# 06_CPU_RAM.net
KiCad netlist of a schematic drawn in Altium Designer
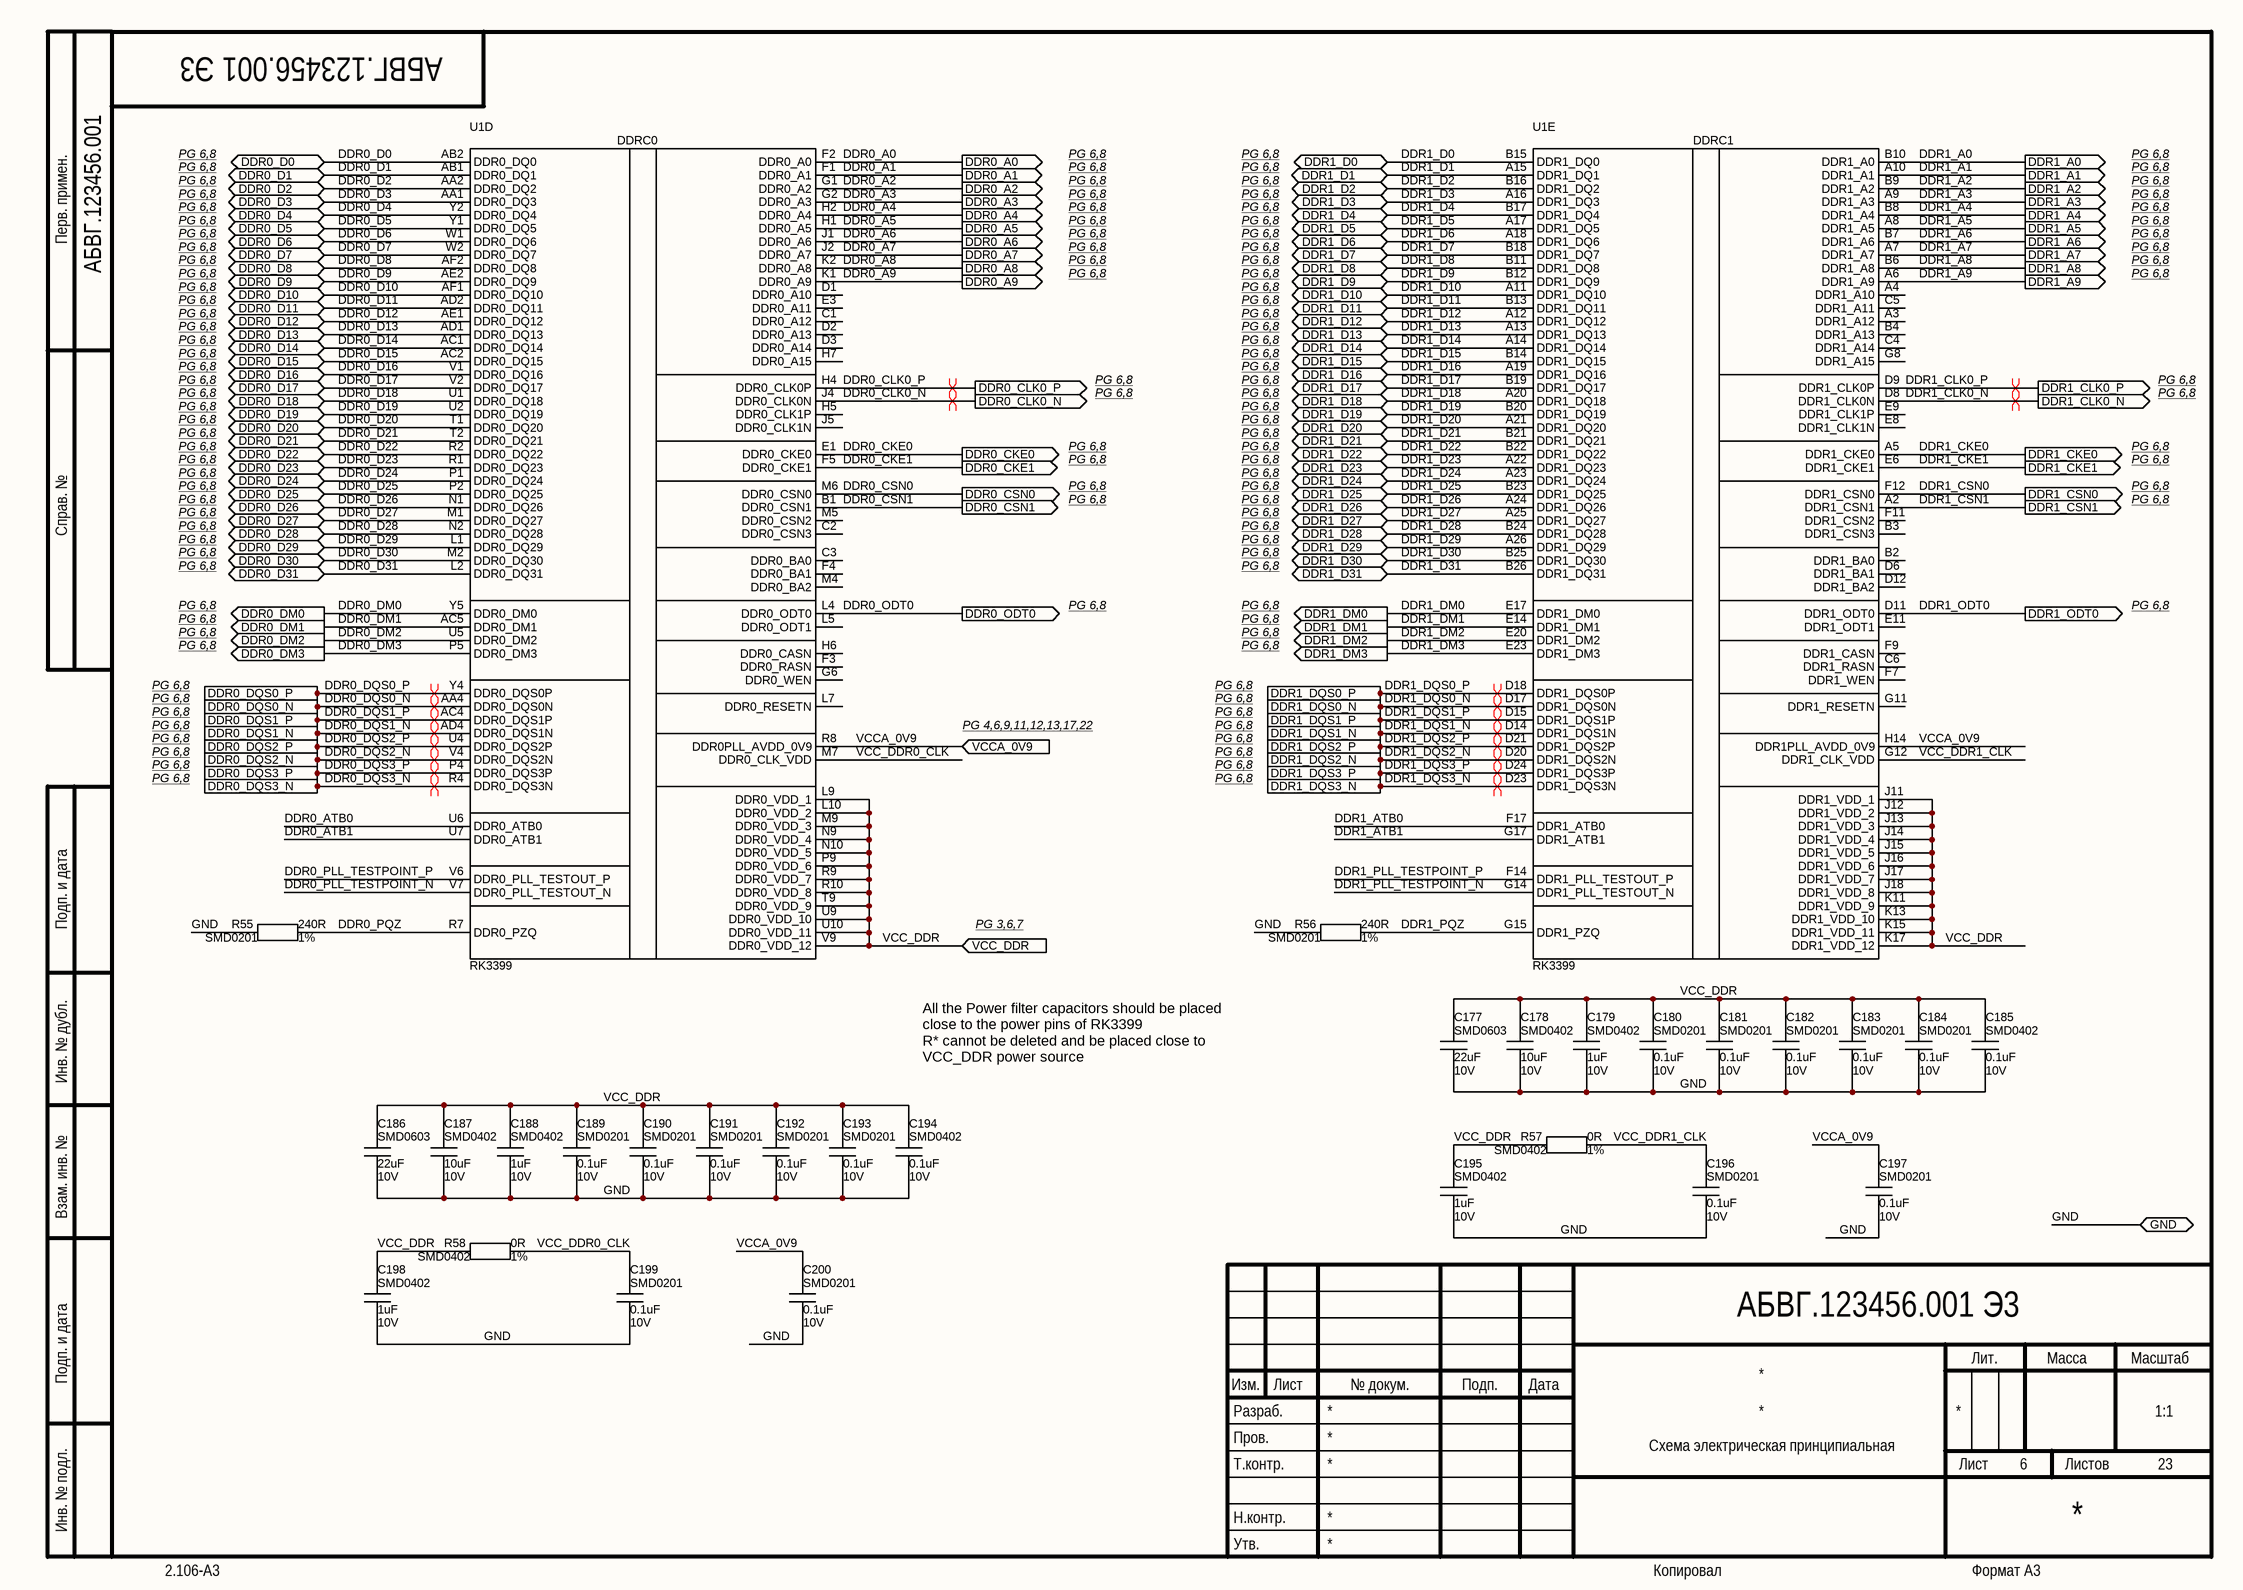
[diagram p0: 06 CPU_RAM.SchDoc]

(export (version "E")
  (design (tool "Eeschema 10.0.6"))
  (components
    (comp (ref "C177")
      (value "22uF")
      (footprint "CAP_SMD_0603")
      (fields
        (field (name "PACKAGE") "SMD0603")
        (field (name "PARTNUMBER") "CL10A226MP8NUNE")
        (field (name "VOLTAGE") "10V")
      )
      (libsource (lib "Didur_SchLib_1") (part "Ceramic_Cap"))
    )
    (comp (ref "C178")
      (value "10uF")
      (footprint "Didur_PcbLib_1:CAP_SMD_0402_small")
      (fields
        (field (name "PACKAGE") "SMD0402")
        (field (name "PARTNUMBER") "CC0402MRX5R6BB106")
        (field (name "VOLTAGE") "10V")
      )
      (libsource (lib "Didur_SchLib_1") (part "Ceramic_Cap"))
    )
    (comp (ref "C179")
      (value "1uF")
      (footprint "Didur_PcbLib_1:CAP_SMD_0402_small")
      (fields
        (field (name "PACKAGE") "SMD0402")
        (field (name "PARTNUMBER") "CC0402KRX5R6BB105")
        (field (name "VOLTAGE") "10V")
      )
      (libsource (lib "Didur_SchLib_1") (part "Ceramic_Cap"))
    )
    (comp (ref "C180")
      (value "0.1uF")
      (footprint "Didur_PcbLib_1:CAP_SMD_0201")
      (fields
        (field (name "PACKAGE") "SMD0201")
        (field (name "PARTNUMBER") "CC0201KRX5R6BB104")
        (field (name "VOLTAGE") "10V")
      )
      (libsource (lib "Didur_SchLib_1") (part "Ceramic_Cap"))
    )
    (comp (ref "C181")
      (value "0.1uF")
      (footprint "Didur_PcbLib_1:CAP_SMD_0201")
      (fields
        (field (name "PACKAGE") "SMD0201")
        (field (name "PARTNUMBER") "CC0201KRX5R6BB104")
        (field (name "VOLTAGE") "10V")
      )
      (libsource (lib "Didur_SchLib_1") (part "Ceramic_Cap"))
    )
    (comp (ref "C182")
      (value "0.1uF")
      (footprint "Didur_PcbLib_1:CAP_SMD_0201")
      (fields
        (field (name "PACKAGE") "SMD0201")
        (field (name "PARTNUMBER") "CC0201KRX5R6BB104")
        (field (name "VOLTAGE") "10V")
      )
      (libsource (lib "Didur_SchLib_1") (part "Ceramic_Cap"))
    )
    (comp (ref "C183")
      (value "0.1uF")
      (footprint "Didur_PcbLib_1:CAP_SMD_0201")
      (fields
        (field (name "PACKAGE") "SMD0201")
        (field (name "PARTNUMBER") "CC0201KRX5R6BB104")
        (field (name "VOLTAGE") "10V")
      )
      (libsource (lib "Didur_SchLib_1") (part "Ceramic_Cap"))
    )
    (comp (ref "C184")
      (value "0.1uF")
      (footprint "Didur_PcbLib_1:CAP_SMD_0201")
      (fields
        (field (name "PACKAGE") "SMD0201")
        (field (name "PARTNUMBER") "CC0201KRX5R6BB104")
        (field (name "VOLTAGE") "10V")
      )
      (libsource (lib "Didur_SchLib_1") (part "Ceramic_Cap"))
    )
    (comp (ref "C185")
      (value "0.1uF")
      (footprint "Didur_PcbLib_1:CAP_SMD_0402")
      (fields
        (field (name "PACKAGE") "SMD0402")
        (field (name "PARTNUMBER") "CC0402KRX5R6BB104")
        (field (name "VOLTAGE") "10V")
      )
      (libsource (lib "Didur_SchLib_1") (part "Ceramic_Cap"))
    )
    (comp (ref "C186")
      (value "22uF")
      (footprint "CAP_SMD_0603")
      (fields
        (field (name "PACKAGE") "SMD0603")
        (field (name "PARTNUMBER") "CL10A226MP8NUNE")
        (field (name "VOLTAGE") "10V")
      )
      (libsource (lib "Didur_SchLib_1") (part "Ceramic_Cap"))
    )
    (comp (ref "C187")
      (value "10uF")
      (footprint "Didur_PcbLib_1:CAP_SMD_0402_small")
      (fields
        (field (name "PACKAGE") "SMD0402")
        (field (name "PARTNUMBER") "CC0402MRX5R6BB106")
        (field (name "VOLTAGE") "10V")
      )
      (libsource (lib "Didur_SchLib_1") (part "Ceramic_Cap"))
    )
    (comp (ref "C188")
      (value "1uF")
      (footprint "Didur_PcbLib_1:CAP_SMD_0402_small")
      (fields
        (field (name "PACKAGE") "SMD0402")
        (field (name "PARTNUMBER") "CC0402KRX5R6BB105")
        (field (name "VOLTAGE") "10V")
      )
      (libsource (lib "Didur_SchLib_1") (part "Ceramic_Cap"))
    )
    (comp (ref "C189")
      (value "0.1uF")
      (footprint "Didur_PcbLib_1:CAP_SMD_0201")
      (fields
        (field (name "PACKAGE") "SMD0201")
        (field (name "PARTNUMBER") "CC0201KRX5R6BB104")
        (field (name "VOLTAGE") "10V")
      )
      (libsource (lib "Didur_SchLib_1") (part "Ceramic_Cap"))
    )
    (comp (ref "C190")
      (value "0.1uF")
      (footprint "Didur_PcbLib_1:CAP_SMD_0201")
      (fields
        (field (name "PACKAGE") "SMD0201")
        (field (name "PARTNUMBER") "CC0201KRX5R6BB104")
        (field (name "VOLTAGE") "10V")
      )
      (libsource (lib "Didur_SchLib_1") (part "Ceramic_Cap"))
    )
    (comp (ref "C191")
      (value "0.1uF")
      (footprint "Didur_PcbLib_1:CAP_SMD_0201")
      (fields
        (field (name "PACKAGE") "SMD0201")
        (field (name "PARTNUMBER") "CC0201KRX5R6BB104")
        (field (name "VOLTAGE") "10V")
      )
      (libsource (lib "Didur_SchLib_1") (part "Ceramic_Cap"))
    )
    (comp (ref "C192")
      (value "0.1uF")
      (footprint "Didur_PcbLib_1:CAP_SMD_0201")
      (fields
        (field (name "PACKAGE") "SMD0201")
        (field (name "PARTNUMBER") "CC0201KRX5R6BB104")
        (field (name "VOLTAGE") "10V")
      )
      (libsource (lib "Didur_SchLib_1") (part "Ceramic_Cap"))
    )
    (comp (ref "C193")
      (value "0.1uF")
      (footprint "Didur_PcbLib_1:CAP_SMD_0201")
      (fields
        (field (name "PACKAGE") "SMD0201")
        (field (name "PARTNUMBER") "CC0201KRX5R6BB104")
        (field (name "VOLTAGE") "10V")
      )
      (libsource (lib "Didur_SchLib_1") (part "Ceramic_Cap"))
    )
    (comp (ref "C194")
      (value "0.1uF")
      (footprint "Didur_PcbLib_1:CAP_SMD_0402")
      (fields
        (field (name "PACKAGE") "SMD0402")
        (field (name "PARTNUMBER") "CC0402KRX5R6BB104")
        (field (name "VOLTAGE") "10V")
      )
      (libsource (lib "Didur_SchLib_1") (part "Ceramic_Cap"))
    )
    (comp (ref "C195")
      (value "1uF")
      (footprint "Didur_PcbLib_1:CAP_SMD_0402_small")
      (fields
        (field (name "PACKAGE") "SMD0402")
        (field (name "PARTNUMBER") "CC0402KRX5R6BB105")
        (field (name "VOLTAGE") "10V")
      )
      (libsource (lib "Didur_SchLib_1") (part "Ceramic_Cap"))
    )
    (comp (ref "C196")
      (value "0.1uF")
      (footprint "Didur_PcbLib_1:CAP_SMD_0201")
      (fields
        (field (name "PACKAGE") "SMD0201")
        (field (name "PARTNUMBER") "CC0201KRX5R6BB104")
        (field (name "VOLTAGE") "10V")
      )
      (libsource (lib "Didur_SchLib_1") (part "Ceramic_Cap"))
    )
    (comp (ref "C197")
      (value "0.1uF")
      (footprint "Didur_PcbLib_1:CAP_SMD_0201")
      (fields
        (field (name "PACKAGE") "SMD0201")
        (field (name "PARTNUMBER") "CC0201KRX5R6BB104")
        (field (name "VOLTAGE") "10V")
      )
      (libsource (lib "Didur_SchLib_1") (part "Ceramic_Cap"))
    )
    (comp (ref "C198")
      (value "1uF")
      (footprint "Didur_PcbLib_1:CAP_SMD_0402_small")
      (fields
        (field (name "PACKAGE") "SMD0402")
        (field (name "PARTNUMBER") "CC0402KRX5R6BB105")
        (field (name "VOLTAGE") "10V")
      )
      (libsource (lib "Didur_SchLib_1") (part "Ceramic_Cap"))
    )
    (comp (ref "C199")
      (value "0.1uF")
      (footprint "Didur_PcbLib_1:CAP_SMD_0201")
      (fields
        (field (name "PACKAGE") "SMD0201")
        (field (name "PARTNUMBER") "CC0201KRX5R6BB104")
        (field (name "VOLTAGE") "10V")
      )
      (libsource (lib "Didur_SchLib_1") (part "Ceramic_Cap"))
    )
    (comp (ref "C200")
      (value "0.1uF")
      (footprint "Didur_PcbLib_1:CAP_SMD_0201")
      (fields
        (field (name "PACKAGE") "SMD0201")
        (field (name "PARTNUMBER") "CC0201KRX5R6BB104")
        (field (name "VOLTAGE") "10V")
      )
      (libsource (lib "Didur_SchLib_1") (part "Ceramic_Cap"))
    )
    (comp (ref "R55")
      (value "240R")
      (footprint "Didur_PcbLib_1:RES_SMD_0201")
      (fields
        (field (name "PACKAGE") "SMD0201")
        (field (name "PARTNUMBER") "RC0201FR-07240RL")
        (field (name "TOLERANCE") "1%")
      )
      (libsource (lib "") (part "Chip_Res_1"))
    )
    (comp (ref "R56")
      (value "240R")
      (footprint "Didur_PcbLib_1:RES_SMD_0201")
      (fields
        (field (name "PACKAGE") "SMD0201")
        (field (name "PARTNUMBER") "RC0201FR-07240RL")
        (field (name "TOLERANCE") "1%")
      )
      (libsource (lib "") (part "Chip_Res_1"))
    )
    (comp (ref "R57")
      (value "0R")
      (footprint "Didur_PcbLib_1:RES_SMD_0402_SMALL")
      (fields
        (field (name "PACKAGE") "SMD0402")
        (field (name "PARTNUMBER") "RC0402FR-070RL")
        (field (name "TOLERANCE") "1%")
      )
      (libsource (lib "Didur_SchLib_1") (part "Chip_Res"))
    )
    (comp (ref "R58")
      (value "0R")
      (footprint "Didur_PcbLib_1:RES_SMD_0402_SMALL")
      (fields
        (field (name "PACKAGE") "SMD0402")
        (field (name "PARTNUMBER") "RC0402FR-070RL")
        (field (name "TOLERANCE") "1%")
      )
      (libsource (lib "Didur_SchLib_1") (part "Chip_Res"))
    )
    (comp (ref "U1")
      (value "RK3399")
      (footprint "BGA828C65P31X31_2100X2100X161N")
      (fields (field (name "Comment") "RK3399_FF"))
      (libsource (lib "Didur_SchLib_1") (part "RK3399_FF"))
    )
  )
  (nets
    (net (code "1") (name "/DDR0_A0") (class "Default")
      (node (ref "U1") (pin "F2") (pinfunction "DDR0_A0_F2") (pintype "passive"))
    )
    (net (code "2") (name "/DDR0_A1") (class "Default")
      (node (ref "U1") (pin "F1") (pinfunction "DDR0_A1_F1") (pintype "passive"))
    )
    (net (code "3") (name "/DDR0_A2") (class "Default")
      (node (ref "U1") (pin "G1") (pinfunction "DDR0_A2_G1") (pintype "passive"))
    )
    (net (code "4") (name "/DDR0_A3") (class "Default")
      (node (ref "U1") (pin "G2") (pinfunction "DDR0_A3_G2") (pintype "passive"))
    )
    (net (code "5") (name "/DDR0_A4") (class "Default")
      (node (ref "U1") (pin "H2") (pinfunction "DDR0_A4_H2") (pintype "passive"))
    )
    (net (code "6") (name "/DDR0_A5") (class "Default")
      (node (ref "U1") (pin "H1") (pinfunction "DDR0_A5_H1") (pintype "passive"))
    )
    (net (code "7") (name "/DDR0_A6") (class "Default")
      (node (ref "U1") (pin "J1") (pinfunction "DDR0_A6_J1") (pintype "passive"))
    )
    (net (code "8") (name "/DDR0_A7") (class "Default")
      (node (ref "U1") (pin "J2") (pinfunction "DDR0_A7_J2") (pintype "passive"))
    )
    (net (code "9") (name "/DDR0_A8") (class "Default")
      (node (ref "U1") (pin "K2") (pinfunction "DDR0_A8_K2") (pintype "passive"))
    )
    (net (code "10") (name "/DDR0_A9") (class "Default")
      (node (ref "U1") (pin "K1") (pinfunction "DDR0_A9_K1") (pintype "passive"))
    )
    (net (code "11") (name "/DDR0_ATB0") (class "Default")
      (node (ref "U1") (pin "U6") (pinfunction "DDR0_ATB0_U6") (pintype "passive"))
    )
    (net (code "12") (name "/DDR0_ATB1") (class "Default")
      (node (ref "U1") (pin "U7") (pinfunction "DDR0_ATB1_U7") (pintype "passive"))
    )
    (net (code "13") (name "/DDR0_CKE0") (class "Default")
      (node (ref "U1") (pin "E1") (pinfunction "DDR0_CKE0_E1") (pintype "passive"))
    )
    (net (code "14") (name "/DDR0_CKE1") (class "Default")
      (node (ref "U1") (pin "F5") (pinfunction "DDR0_CKE1_F5") (pintype "passive"))
    )
    (net (code "15") (name "/DDR0_CLK0_N") (class "Default")
      (node (ref "U1") (pin "J4") (pinfunction "DDR0_CLK0N_J4") (pintype "passive"))
    )
    (net (code "16") (name "/DDR0_CLK0_P") (class "Default")
      (node (ref "U1") (pin "H4") (pinfunction "DDR0_CLK0P_H4") (pintype "passive"))
    )
    (net (code "17") (name "/DDR0_CSN0") (class "Default")
      (node (ref "U1") (pin "M6") (pinfunction "DDR0_CSN0_M6") (pintype "passive"))
    )
    (net (code "18") (name "/DDR0_CSN1") (class "Default")
      (node (ref "U1") (pin "B1") (pinfunction "DDR0_CSN1_B1") (pintype "passive"))
    )
    (net (code "19") (name "/DDR0_D0") (class "Default")
      (node (ref "U1") (pin "AB2") (pinfunction "DDR0_DQ0_AB2") (pintype "passive"))
    )
    (net (code "20") (name "/DDR0_D1") (class "Default")
      (node (ref "U1") (pin "AB1") (pinfunction "DDR0_DQ1_AB1") (pintype "passive"))
    )
    (net (code "21") (name "/DDR0_D2") (class "Default")
      (node (ref "U1") (pin "AA2") (pinfunction "DDR0_DQ2_AA2") (pintype "passive"))
    )
    (net (code "22") (name "/DDR0_D3") (class "Default")
      (node (ref "U1") (pin "AA1") (pinfunction "DDR0_DQ3_AA1") (pintype "passive"))
    )
    (net (code "23") (name "/DDR0_D4") (class "Default")
      (node (ref "U1") (pin "Y2") (pinfunction "DDR0_DQ4_Y2") (pintype "passive"))
    )
    (net (code "24") (name "/DDR0_D5") (class "Default")
      (node (ref "U1") (pin "Y1") (pinfunction "DDR0_DQ5_Y1") (pintype "passive"))
    )
    (net (code "25") (name "/DDR0_D6") (class "Default")
      (node (ref "U1") (pin "W1") (pinfunction "DDR0_DQ6_W1") (pintype "passive"))
    )
    (net (code "26") (name "/DDR0_D7") (class "Default")
      (node (ref "U1") (pin "W2") (pinfunction "DDR0_DQ7_W2") (pintype "passive"))
    )
    (net (code "27") (name "/DDR0_D8") (class "Default")
      (node (ref "U1") (pin "AF2") (pinfunction "DDR0_DQ8_AF2") (pintype "passive"))
    )
    (net (code "28") (name "/DDR0_D9") (class "Default")
      (node (ref "U1") (pin "AE2") (pinfunction "DDR0_DQ9_AE2") (pintype "passive"))
    )
    (net (code "29") (name "/DDR0_D10") (class "Default")
      (node (ref "U1") (pin "AF1") (pinfunction "DDR0_DQ10_AF1") (pintype "passive"))
    )
    (net (code "30") (name "/DDR0_D11") (class "Default")
      (node (ref "U1") (pin "AD2") (pinfunction "DDR0_DQ11_AD2") (pintype "passive"))
    )
    (net (code "31") (name "/DDR0_D12") (class "Default")
      (node (ref "U1") (pin "AE1") (pinfunction "DDR0_DQ12_AE1") (pintype "passive"))
    )
    (net (code "32") (name "/DDR0_D13") (class "Default")
      (node (ref "U1") (pin "AD1") (pinfunction "DDR0_DQ13_AD1") (pintype "passive"))
    )
    (net (code "33") (name "/DDR0_D14") (class "Default")
      (node (ref "U1") (pin "AC1") (pinfunction "DDR0_DQ14_AC1") (pintype "passive"))
    )
    (net (code "34") (name "/DDR0_D15") (class "Default")
      (node (ref "U1") (pin "AC2") (pinfunction "DDR0_DQ15_AC2") (pintype "passive"))
    )
    (net (code "35") (name "/DDR0_D16") (class "Default")
      (node (ref "U1") (pin "V1") (pinfunction "DDR0_DQ16_V1") (pintype "passive"))
    )
    (net (code "36") (name "/DDR0_D17") (class "Default")
      (node (ref "U1") (pin "V2") (pinfunction "DDR0_DQ17_V2") (pintype "passive"))
    )
    (net (code "37") (name "/DDR0_D18") (class "Default")
      (node (ref "U1") (pin "U1") (pinfunction "DDR0_DQ18_U1") (pintype "passive"))
    )
    (net (code "38") (name "/DDR0_D19") (class "Default")
      (node (ref "U1") (pin "U2") (pinfunction "DDR0_DQ19_U2") (pintype "passive"))
    )
    (net (code "39") (name "/DDR0_D20") (class "Default")
      (node (ref "U1") (pin "T1") (pinfunction "DDR0_DQ20_T1") (pintype "passive"))
    )
    (net (code "40") (name "/DDR0_D21") (class "Default")
      (node (ref "U1") (pin "T2") (pinfunction "DDR0_DQ21_T2") (pintype "passive"))
    )
    (net (code "41") (name "/DDR0_D22") (class "Default")
      (node (ref "U1") (pin "R2") (pinfunction "DDR0_DQ22_R2") (pintype "passive"))
    )
    (net (code "42") (name "/DDR0_D23") (class "Default")
      (node (ref "U1") (pin "R1") (pinfunction "DDR0_DQ23_R1") (pintype "passive"))
    )
    (net (code "43") (name "/DDR0_D24") (class "Default")
      (node (ref "U1") (pin "P1") (pinfunction "DDR0_DQ24_P1") (pintype "passive"))
    )
    (net (code "44") (name "/DDR0_D25") (class "Default")
      (node (ref "U1") (pin "P2") (pinfunction "DDR0_DQ25_P2") (pintype "passive"))
    )
    (net (code "45") (name "/DDR0_D26") (class "Default")
      (node (ref "U1") (pin "N1") (pinfunction "DDR0_DQ26_N1") (pintype "passive"))
    )
    (net (code "46") (name "/DDR0_D27") (class "Default")
      (node (ref "U1") (pin "M1") (pinfunction "DDR0_DQ27_M1") (pintype "passive"))
    )
    (net (code "47") (name "/DDR0_D28") (class "Default")
      (node (ref "U1") (pin "N2") (pinfunction "DDR0_DQ28_N2") (pintype "passive"))
    )
    (net (code "48") (name "/DDR0_D29") (class "Default")
      (node (ref "U1") (pin "L1") (pinfunction "DDR0_DQ29_L1") (pintype "passive"))
    )
    (net (code "49") (name "/DDR0_D30") (class "Default")
      (node (ref "U1") (pin "M2") (pinfunction "DDR0_DQ30_M2") (pintype "passive"))
    )
    (net (code "50") (name "/DDR0_D31") (class "Default")
      (node (ref "U1") (pin "L2") (pinfunction "DDR0_DQ31_L2") (pintype "passive"))
    )
    (net (code "51") (name "/DDR0_DM0") (class "Default")
      (node (ref "U1") (pin "Y5") (pinfunction "DDR0_DM0_Y5") (pintype "passive"))
    )
    (net (code "52") (name "/DDR0_DM1") (class "Default")
      (node (ref "U1") (pin "AC5") (pinfunction "DDR0_DM1_AC5") (pintype "passive"))
    )
    (net (code "53") (name "/DDR0_DM2") (class "Default")
      (node (ref "U1") (pin "U5") (pinfunction "DDR0_DM2_U5") (pintype "passive"))
    )
    (net (code "54") (name "/DDR0_DM3") (class "Default")
      (node (ref "U1") (pin "P5") (pinfunction "DDR0_DM3_P5") (pintype "passive"))
    )
    (net (code "55") (name "/DDR0_DQS0_N") (class "Default")
      (node (ref "U1") (pin "AA4") (pinfunction "DDR0_DQS0N_AA4") (pintype "passive"))
    )
    (net (code "56") (name "/DDR0_DQS0_P") (class "Default")
      (node (ref "U1") (pin "Y4") (pinfunction "DDR0_DQS0P_Y4") (pintype "passive"))
    )
    (net (code "57") (name "/DDR0_DQS1_N") (class "Default")
      (node (ref "U1") (pin "AD4") (pinfunction "DDR0_DQS1N_AD4") (pintype "passive"))
    )
    (net (code "58") (name "/DDR0_DQS1_P") (class "Default")
      (node (ref "U1") (pin "AC4") (pinfunction "DDR0_DQS1P_AC4") (pintype "passive"))
    )
    (net (code "59") (name "/DDR0_DQS2_N") (class "Default")
      (node (ref "U1") (pin "V4") (pinfunction "DDR0_DQS2N_V4") (pintype "passive"))
    )
    (net (code "60") (name "/DDR0_DQS2_P") (class "Default")
      (node (ref "U1") (pin "U4") (pinfunction "DDR0_DQS2P_U4") (pintype "passive"))
    )
    (net (code "61") (name "/DDR0_DQS3_N") (class "Default")
      (node (ref "U1") (pin "R4") (pinfunction "DDR0_DQS3N_R4") (pintype "passive"))
    )
    (net (code "62") (name "/DDR0_DQS3_P") (class "Default")
      (node (ref "U1") (pin "P4") (pinfunction "DDR0_DQS3P_P4") (pintype "passive"))
    )
    (net (code "63") (name "/DDR0_ODT0") (class "Default")
      (node (ref "U1") (pin "L4") (pinfunction "DDR0_ODT0_L4") (pintype "passive"))
    )
    (net (code "64") (name "/DDR0_PLL_TESTPOINT_N") (class "Default")
      (node (ref "U1") (pin "V7") (pinfunction "DDR0_PLL_TESTOUT_N_V7") (pintype "passive"))
    )
    (net (code "65") (name "/DDR0_PLL_TESTPOINT_P") (class "Default")
      (node (ref "U1") (pin "V6") (pinfunction "DDR0_PLL_TESTOUT_P_V6") (pintype "passive"))
    )
    (net (code "66") (name "/DDR0_PQZ") (class "Default")
      (node (ref "R55") (pin "1") (pinfunction "1_1") (pintype "passive"))
      (node (ref "U1") (pin "R7") (pinfunction "DDR0_PZQ_R7") (pintype "passive"))
    )
    (net (code "67") (name "/DDR1_A0") (class "Default")
      (node (ref "U1") (pin "B10") (pinfunction "DDR1_A0_B10") (pintype "passive"))
    )
    (net (code "68") (name "/DDR1_A1") (class "Default")
      (node (ref "U1") (pin "A10") (pinfunction "DDR1_A1_A10") (pintype "passive"))
    )
    (net (code "69") (name "/DDR1_A2") (class "Default")
      (node (ref "U1") (pin "B9") (pinfunction "DDR1_A2_B9") (pintype "passive"))
    )
    (net (code "70") (name "/DDR1_A3") (class "Default")
      (node (ref "U1") (pin "A9") (pinfunction "DDR1_A3_A9") (pintype "passive"))
    )
    (net (code "71") (name "/DDR1_A4") (class "Default")
      (node (ref "U1") (pin "B8") (pinfunction "DDR1_A4_B8") (pintype "passive"))
    )
    (net (code "72") (name "/DDR1_A5") (class "Default")
      (node (ref "U1") (pin "A8") (pinfunction "DDR1_A5_A8") (pintype "passive"))
    )
    (net (code "73") (name "/DDR1_A6") (class "Default")
      (node (ref "U1") (pin "B7") (pinfunction "DDR1_A6_B7") (pintype "passive"))
    )
    (net (code "74") (name "/DDR1_A7") (class "Default")
      (node (ref "U1") (pin "A7") (pinfunction "DDR1_A7_A7") (pintype "passive"))
    )
    (net (code "75") (name "/DDR1_A8") (class "Default")
      (node (ref "U1") (pin "B6") (pinfunction "DDR1_A8_B6") (pintype "passive"))
    )
    (net (code "76") (name "/DDR1_A9") (class "Default")
      (node (ref "U1") (pin "A6") (pinfunction "DDR1_A9_A6") (pintype "passive"))
    )
    (net (code "77") (name "/DDR1_ATB0") (class "Default")
      (node (ref "U1") (pin "F17") (pinfunction "DDR1_ATB0_F17") (pintype "passive"))
    )
    (net (code "78") (name "/DDR1_ATB1") (class "Default")
      (node (ref "U1") (pin "G17") (pinfunction "DDR1_ATB1_G17") (pintype "passive"))
    )
    (net (code "79") (name "/DDR1_CKE0") (class "Default")
      (node (ref "U1") (pin "A5") (pinfunction "DDR1_CKE0_A5") (pintype "passive"))
    )
    (net (code "80") (name "/DDR1_CKE1") (class "Default")
      (node (ref "U1") (pin "E6") (pinfunction "DDR1_CKE1_E6") (pintype "passive"))
    )
    (net (code "81") (name "/DDR1_CLK0_N") (class "Default")
      (node (ref "U1") (pin "D8") (pinfunction "DDR1_CLK0N_D8") (pintype "passive"))
    )
    (net (code "82") (name "/DDR1_CLK0_P") (class "Default")
      (node (ref "U1") (pin "D9") (pinfunction "DDR1_CLK0P_D9") (pintype "passive"))
    )
    (net (code "83") (name "/DDR1_CSN0") (class "Default")
      (node (ref "U1") (pin "F12") (pinfunction "DDR1_CSN0_F12") (pintype "passive"))
    )
    (net (code "84") (name "/DDR1_CSN1") (class "Default")
      (node (ref "U1") (pin "A2") (pinfunction "DDR1_CSN1_A2") (pintype "passive"))
    )
    (net (code "85") (name "/DDR1_D0") (class "Default")
      (node (ref "U1") (pin "B15") (pinfunction "DDR1_DQ0_B15") (pintype "passive"))
    )
    (net (code "86") (name "/DDR1_D1") (class "Default")
      (node (ref "U1") (pin "A15") (pinfunction "DDR1_DQ1_A15") (pintype "passive"))
    )
    (net (code "87") (name "/DDR1_D2") (class "Default")
      (node (ref "U1") (pin "B16") (pinfunction "DDR1_DQ2_B16") (pintype "passive"))
    )
    (net (code "88") (name "/DDR1_D3") (class "Default")
      (node (ref "U1") (pin "A16") (pinfunction "DDR1_DQ3_A16") (pintype "passive"))
    )
    (net (code "89") (name "/DDR1_D4") (class "Default")
      (node (ref "U1") (pin "B17") (pinfunction "DDR1_DQ4_B17") (pintype "passive"))
    )
    (net (code "90") (name "/DDR1_D5") (class "Default")
      (node (ref "U1") (pin "A17") (pinfunction "DDR1_DQ5_A17") (pintype "passive"))
    )
    (net (code "91") (name "/DDR1_D6") (class "Default")
      (node (ref "U1") (pin "A18") (pinfunction "DDR1_DQ6_A18") (pintype "passive"))
    )
    (net (code "92") (name "/DDR1_D7") (class "Default")
      (node (ref "U1") (pin "B18") (pinfunction "DDR1_DQ7_B18") (pintype "passive"))
    )
    (net (code "93") (name "/DDR1_D8") (class "Default")
      (node (ref "U1") (pin "B11") (pinfunction "DDR1_DQ8_B11") (pintype "passive"))
    )
    (net (code "94") (name "/DDR1_D9") (class "Default")
      (node (ref "U1") (pin "B12") (pinfunction "DDR1_DQ9_B12") (pintype "passive"))
    )
    (net (code "95") (name "/DDR1_D10") (class "Default")
      (node (ref "U1") (pin "A11") (pinfunction "DDR1_DQ10_A11") (pintype "passive"))
    )
    (net (code "96") (name "/DDR1_D11") (class "Default")
      (node (ref "U1") (pin "B13") (pinfunction "DDR1_DQ11_B13") (pintype "passive"))
    )
    (net (code "97") (name "/DDR1_D12") (class "Default")
      (node (ref "U1") (pin "A12") (pinfunction "DDR1_DQ12_A12") (pintype "passive"))
    )
    (net (code "98") (name "/DDR1_D13") (class "Default")
      (node (ref "U1") (pin "A13") (pinfunction "DDR1_DQ13_A13") (pintype "passive"))
    )
    (net (code "99") (name "/DDR1_D14") (class "Default")
      (node (ref "U1") (pin "A14") (pinfunction "DDR1_DQ14_A14") (pintype "passive"))
    )
    (net (code "100") (name "/DDR1_D15") (class "Default")
      (node (ref "U1") (pin "B14") (pinfunction "DDR1_DQ15_B14") (pintype "passive"))
    )
    (net (code "101") (name "/DDR1_D16") (class "Default")
      (node (ref "U1") (pin "A19") (pinfunction "DDR1_DQ16_A19") (pintype "passive"))
    )
    (net (code "102") (name "/DDR1_D17") (class "Default")
      (node (ref "U1") (pin "B19") (pinfunction "DDR1_DQ17_B19") (pintype "passive"))
    )
    (net (code "103") (name "/DDR1_D18") (class "Default")
      (node (ref "U1") (pin "A20") (pinfunction "DDR1_DQ18_A20") (pintype "passive"))
    )
    (net (code "104") (name "/DDR1_D19") (class "Default")
      (node (ref "U1") (pin "B20") (pinfunction "DDR1_DQ19_B20") (pintype "passive"))
    )
    (net (code "105") (name "/DDR1_D20") (class "Default")
      (node (ref "U1") (pin "A21") (pinfunction "DDR1_DQ20_A21") (pintype "passive"))
    )
    (net (code "106") (name "/DDR1_D21") (class "Default")
      (node (ref "U1") (pin "B21") (pinfunction "DDR1_DQ21_B21") (pintype "passive"))
    )
    (net (code "107") (name "/DDR1_D22") (class "Default")
      (node (ref "U1") (pin "B22") (pinfunction "DDR1_DQ22_B22") (pintype "passive"))
    )
    (net (code "108") (name "/DDR1_D23") (class "Default")
      (node (ref "U1") (pin "A22") (pinfunction "DDR1_DQ23_A22") (pintype "passive"))
    )
    (net (code "109") (name "/DDR1_D24") (class "Default")
      (node (ref "U1") (pin "A23") (pinfunction "DDR1_DQ24_A23") (pintype "passive"))
    )
    (net (code "110") (name "/DDR1_D25") (class "Default")
      (node (ref "U1") (pin "B23") (pinfunction "DDR1_DQ25_B23") (pintype "passive"))
    )
    (net (code "111") (name "/DDR1_D26") (class "Default")
      (node (ref "U1") (pin "A24") (pinfunction "DDR1_DQ26_A24") (pintype "passive"))
    )
    (net (code "112") (name "/DDR1_D27") (class "Default")
      (node (ref "U1") (pin "A25") (pinfunction "DDR1_DQ27_A25") (pintype "passive"))
    )
    (net (code "113") (name "/DDR1_D28") (class "Default")
      (node (ref "U1") (pin "B24") (pinfunction "DDR1_DQ28_B24") (pintype "passive"))
    )
    (net (code "114") (name "/DDR1_D29") (class "Default")
      (node (ref "U1") (pin "A26") (pinfunction "DDR1_DQ29_A26") (pintype "passive"))
    )
    (net (code "115") (name "/DDR1_D30") (class "Default")
      (node (ref "U1") (pin "B25") (pinfunction "DDR1_DQ30_B25") (pintype "passive"))
    )
    (net (code "116") (name "/DDR1_D31") (class "Default")
      (node (ref "U1") (pin "B26") (pinfunction "DDR1_DQ31_B26") (pintype "passive"))
    )
    (net (code "117") (name "/DDR1_DM0") (class "Default")
      (node (ref "U1") (pin "E17") (pinfunction "DDR1_DM0_E17") (pintype "passive"))
    )
    (net (code "118") (name "/DDR1_DM1") (class "Default")
      (node (ref "U1") (pin "E14") (pinfunction "DDR1_DM1_E14") (pintype "passive"))
    )
    (net (code "119") (name "/DDR1_DM2") (class "Default")
      (node (ref "U1") (pin "E20") (pinfunction "DDR1_DM2_E20") (pintype "passive"))
    )
    (net (code "120") (name "/DDR1_DM3") (class "Default")
      (node (ref "U1") (pin "E23") (pinfunction "DDR1_DM3_E23") (pintype "passive"))
    )
    (net (code "121") (name "/DDR1_DQS0_N") (class "Default")
      (node (ref "U1") (pin "D17") (pinfunction "DDR1_DQS0N_D17") (pintype "passive"))
    )
    (net (code "122") (name "/DDR1_DQS0_P") (class "Default")
      (node (ref "U1") (pin "D18") (pinfunction "DDR1_DQS0P_D18") (pintype "passive"))
    )
    (net (code "123") (name "/DDR1_DQS1_N") (class "Default")
      (node (ref "U1") (pin "D14") (pinfunction "DDR1_DQS1N_D14") (pintype "passive"))
    )
    (net (code "124") (name "/DDR1_DQS1_P") (class "Default")
      (node (ref "U1") (pin "D15") (pinfunction "DDR1_DQS1P_D15") (pintype "passive"))
    )
    (net (code "125") (name "/DDR1_DQS2_N") (class "Default")
      (node (ref "U1") (pin "D20") (pinfunction "DDR1_DQS2N_D20") (pintype "passive"))
    )
    (net (code "126") (name "/DDR1_DQS2_P") (class "Default")
      (node (ref "U1") (pin "D21") (pinfunction "DDR1_DQS2P_D21") (pintype "passive"))
    )
    (net (code "127") (name "/DDR1_DQS3_N") (class "Default")
      (node (ref "U1") (pin "D23") (pinfunction "DDR1_DQS3N_D23") (pintype "passive"))
    )
    (net (code "128") (name "/DDR1_DQS3_P") (class "Default")
      (node (ref "U1") (pin "D24") (pinfunction "DDR1_DQS3P_D24") (pintype "passive"))
    )
    (net (code "129") (name "/DDR1_ODT0") (class "Default")
      (node (ref "U1") (pin "D11") (pinfunction "DDR1_ODT0_D11") (pintype "passive"))
    )
    (net (code "130") (name "/DDR1_PLL_TESTPOINT_N") (class "Default")
      (node (ref "U1") (pin "G14") (pinfunction "DDR1_PLL_TESTOUT_N_G14") (pintype "passive"))
    )
    (net (code "131") (name "/DDR1_PLL_TESTPOINT_P") (class "Default")
      (node (ref "U1") (pin "F14") (pinfunction "DDR1_PLL_TESTOUT_P_F14") (pintype "passive"))
    )
    (net (code "132") (name "/DDR1_PQZ") (class "Default")
      (node (ref "R56") (pin "1") (pinfunction "1_1") (pintype "passive"))
      (node (ref "U1") (pin "G15") (pinfunction "DDR1_PZQ_G15") (pintype "passive"))
    )
    (net (code "133") (name "/GND") (class "Default")
      (node (ref "C177") (pin "1") (pinfunction "1_1") (pintype "power_in"))
      (node (ref "C178") (pin "2") (pinfunction "2_2") (pintype "power_in"))
      (node (ref "C179") (pin "2") (pinfunction "2_2") (pintype "power_in"))
      (node (ref "C180") (pin "2") (pinfunction "2_2") (pintype "power_in"))
      (node (ref "C181") (pin "2") (pinfunction "2_2") (pintype "power_in"))
      (node (ref "C182") (pin "2") (pinfunction "2_2") (pintype "power_in"))
      (node (ref "C183") (pin "2") (pinfunction "2_2") (pintype "power_in"))
      (node (ref "C184") (pin "2") (pinfunction "2_2") (pintype "power_in"))
      (node (ref "C185") (pin "2") (pinfunction "2_2") (pintype "power_in"))
      (node (ref "C186") (pin "1") (pinfunction "1_1") (pintype "power_in"))
      (node (ref "C187") (pin "2") (pinfunction "2_2") (pintype "power_in"))
      (node (ref "C188") (pin "2") (pinfunction "2_2") (pintype "power_in"))
      (node (ref "C189") (pin "2") (pinfunction "2_2") (pintype "power_in"))
      (node (ref "C190") (pin "2") (pinfunction "2_2") (pintype "power_in"))
      (node (ref "C191") (pin "2") (pinfunction "2_2") (pintype "power_in"))
      (node (ref "C192") (pin "2") (pinfunction "2_2") (pintype "power_in"))
      (node (ref "C193") (pin "2") (pinfunction "2_2") (pintype "power_in"))
      (node (ref "C194") (pin "2") (pinfunction "2_2") (pintype "power_in"))
      (node (ref "C195") (pin "2") (pinfunction "2_2") (pintype "power_in"))
      (node (ref "C196") (pin "2") (pinfunction "2_2") (pintype "power_in"))
      (node (ref "C197") (pin "2") (pinfunction "2_2") (pintype "power_in"))
      (node (ref "C198") (pin "2") (pinfunction "2_2") (pintype "power_in"))
      (node (ref "C199") (pin "2") (pinfunction "2_2") (pintype "power_in"))
      (node (ref "C200") (pin "2") (pinfunction "2_2") (pintype "power_in"))
      (node (ref "R55") (pin "2") (pinfunction "2_2") (pintype "passive"))
      (node (ref "R56") (pin "2") (pinfunction "2_2") (pintype "passive"))
    )
    (net (code "134") (name "/VCCA_0V9") (class "Default")
      (node (ref "C197") (pin "1") (pinfunction "1_1") (pintype "power_in"))
      (node (ref "C200") (pin "1") (pinfunction "1_1") (pintype "power_in"))
      (node (ref "U1") (pin "H14") (pinfunction "DDR1PLL_AVDD_0V9_H14") (pintype "passive"))
      (node (ref "U1") (pin "R8") (pinfunction "DDR0PLL_AVDD_0V9_R8") (pintype "passive"))
    )
    (net (code "135") (name "/VCC_DDR") (class "Default")
      (node (ref "C177") (pin "2") (pinfunction "2_2") (pintype "power_in"))
      (node (ref "C178") (pin "1") (pinfunction "1_1") (pintype "power_in"))
      (node (ref "C179") (pin "1") (pinfunction "1_1") (pintype "power_in"))
      (node (ref "C180") (pin "1") (pinfunction "1_1") (pintype "power_in"))
      (node (ref "C181") (pin "1") (pinfunction "1_1") (pintype "power_in"))
      (node (ref "C182") (pin "1") (pinfunction "1_1") (pintype "power_in"))
      (node (ref "C183") (pin "1") (pinfunction "1_1") (pintype "power_in"))
      (node (ref "C184") (pin "1") (pinfunction "1_1") (pintype "power_in"))
      (node (ref "C185") (pin "1") (pinfunction "1_1") (pintype "power_in"))
      (node (ref "C186") (pin "2") (pinfunction "2_2") (pintype "power_in"))
      (node (ref "C187") (pin "1") (pinfunction "1_1") (pintype "power_in"))
      (node (ref "C188") (pin "1") (pinfunction "1_1") (pintype "power_in"))
      (node (ref "C189") (pin "1") (pinfunction "1_1") (pintype "power_in"))
      (node (ref "C190") (pin "1") (pinfunction "1_1") (pintype "power_in"))
      (node (ref "C191") (pin "1") (pinfunction "1_1") (pintype "power_in"))
      (node (ref "C192") (pin "1") (pinfunction "1_1") (pintype "power_in"))
      (node (ref "C193") (pin "1") (pinfunction "1_1") (pintype "power_in"))
      (node (ref "C194") (pin "1") (pinfunction "1_1") (pintype "power_in"))
      (node (ref "C195") (pin "1") (pinfunction "1_1") (pintype "power_in"))
      (node (ref "C198") (pin "1") (pinfunction "1_1") (pintype "power_in"))
      (node (ref "R57") (pin "1") (pinfunction "1_1") (pintype "passive"))
      (node (ref "R58") (pin "1") (pinfunction "1_1") (pintype "passive"))
      (node (ref "U1") (pin "J11") (pinfunction "DDR1_VDD_1_J11") (pintype "passive"))
      (node (ref "U1") (pin "J12") (pinfunction "DDR1_VDD_2_J12") (pintype "passive"))
      (node (ref "U1") (pin "J13") (pinfunction "DDR1_VDD_3_J13") (pintype "passive"))
      (node (ref "U1") (pin "J14") (pinfunction "DDR1_VDD_4_J14") (pintype "passive"))
      (node (ref "U1") (pin "J15") (pinfunction "DDR1_VDD_5_J15") (pintype "passive"))
      (node (ref "U1") (pin "J16") (pinfunction "DDR1_VDD_6_J16") (pintype "passive"))
      (node (ref "U1") (pin "J17") (pinfunction "DDR1_VDD_7_J17") (pintype "passive"))
      (node (ref "U1") (pin "J18") (pinfunction "DDR1_VDD_8_J18") (pintype "passive"))
      (node (ref "U1") (pin "K11") (pinfunction "DDR1_VDD_9_K11") (pintype "passive"))
      (node (ref "U1") (pin "K13") (pinfunction "DDR1_VDD_10_K13") (pintype "passive"))
      (node (ref "U1") (pin "K15") (pinfunction "DDR1_VDD_11_K15") (pintype "passive"))
      (node (ref "U1") (pin "K17") (pinfunction "DDR1_VDD_12_K17") (pintype "passive"))
      (node (ref "U1") (pin "L10") (pinfunction "DDR0_VDD_2_L10") (pintype "passive"))
      (node (ref "U1") (pin "L9") (pinfunction "DDR0_VDD_1_L9") (pintype "passive"))
      (node (ref "U1") (pin "M9") (pinfunction "DDR0_VDD_3_M9") (pintype "passive"))
      (node (ref "U1") (pin "N10") (pinfunction "DDR0_VDD_5_N10") (pintype "passive"))
      (node (ref "U1") (pin "N9") (pinfunction "DDR0_VDD_4_N9") (pintype "passive"))
      (node (ref "U1") (pin "P9") (pinfunction "DDR0_VDD_6_P9") (pintype "passive"))
      (node (ref "U1") (pin "R10") (pinfunction "DDR0_VDD_8_R10") (pintype "passive"))
      (node (ref "U1") (pin "R9") (pinfunction "DDR0_VDD_7_R9") (pintype "passive"))
      (node (ref "U1") (pin "T9") (pinfunction "DDR0_VDD_9_T9") (pintype "passive"))
      (node (ref "U1") (pin "U10") (pinfunction "DDR0_VDD_11_U10") (pintype "passive"))
      (node (ref "U1") (pin "U9") (pinfunction "DDR0_VDD_10_U9") (pintype "passive"))
      (node (ref "U1") (pin "V9") (pinfunction "DDR0_VDD_12_V9") (pintype "passive"))
    )
    (net (code "136") (name "/VCC_DDR0_CLK") (class "Default")
      (node (ref "C199") (pin "1") (pinfunction "1_1") (pintype "power_in"))
      (node (ref "R58") (pin "2") (pinfunction "2_2") (pintype "passive"))
      (node (ref "U1") (pin "M7") (pinfunction "DDR0_CLK_VDD_M7") (pintype "passive"))
    )
    (net (code "137") (name "/VCC_DDR1_CLK") (class "Default")
      (node (ref "C196") (pin "1") (pinfunction "1_1") (pintype "power_in"))
      (node (ref "R57") (pin "2") (pinfunction "2_2") (pintype "passive"))
      (node (ref "U1") (pin "G12") (pinfunction "DDR1_CLK_VDD_G12") (pintype "passive"))
    )
    (net (code "138") (name "unconnected-(U1D-DDR0_A10-PadD1)") (class "Default")
      (node (ref "U1") (pin "D1") (pinfunction "DDR0_A10_D1") (pintype "passive"))
    )
    (net (code "139") (name "unconnected-(U1D-DDR0_A11-PadE3)") (class "Default")
      (node (ref "U1") (pin "E3") (pinfunction "DDR0_A11_E3") (pintype "passive"))
    )
    (net (code "140") (name "unconnected-(U1D-DDR0_A12-PadC1)") (class "Default")
      (node (ref "U1") (pin "C1") (pinfunction "DDR0_A12_C1") (pintype "passive"))
    )
    (net (code "141") (name "unconnected-(U1D-DDR0_A13-PadD2)") (class "Default")
      (node (ref "U1") (pin "D2") (pinfunction "DDR0_A13_D2") (pintype "passive"))
    )
    (net (code "142") (name "unconnected-(U1D-DDR0_A14-PadD3)") (class "Default")
      (node (ref "U1") (pin "D3") (pinfunction "DDR0_A14_D3") (pintype "passive"))
    )
    (net (code "143") (name "unconnected-(U1D-DDR0_A15-PadH7)") (class "Default")
      (node (ref "U1") (pin "H7") (pinfunction "DDR0_A15_H7") (pintype "passive"))
    )
    (net (code "144") (name "unconnected-(U1D-DDR0_BA0-PadC3)") (class "Default")
      (node (ref "U1") (pin "C3") (pinfunction "DDR0_BA0_C3") (pintype "passive"))
    )
    (net (code "145") (name "unconnected-(U1D-DDR0_BA1-PadF4)") (class "Default")
      (node (ref "U1") (pin "F4") (pinfunction "DDR0_BA1_F4") (pintype "passive"))
    )
    (net (code "146") (name "unconnected-(U1D-DDR0_BA2-PadM4)") (class "Default")
      (node (ref "U1") (pin "M4") (pinfunction "DDR0_BA2_M4") (pintype "passive"))
    )
    (net (code "147") (name "unconnected-(U1D-DDR0_CASN-PadH6)") (class "Default")
      (node (ref "U1") (pin "H6") (pinfunction "DDR0_CASN_H6") (pintype "passive"))
    )
    (net (code "148") (name "unconnected-(U1D-DDR0_CLK1N-PadJ5)") (class "Default")
      (node (ref "U1") (pin "J5") (pinfunction "DDR0_CLK1N_J5") (pintype "passive"))
    )
    (net (code "149") (name "unconnected-(U1D-DDR0_CLK1P-PadH5)") (class "Default")
      (node (ref "U1") (pin "H5") (pinfunction "DDR0_CLK1P_H5") (pintype "passive"))
    )
    (net (code "150") (name "unconnected-(U1D-DDR0_CSN2-PadM5)") (class "Default")
      (node (ref "U1") (pin "M5") (pinfunction "DDR0_CSN2_M5") (pintype "passive"))
    )
    (net (code "151") (name "unconnected-(U1D-DDR0_CSN3-PadC2)") (class "Default")
      (node (ref "U1") (pin "C2") (pinfunction "DDR0_CSN3_C2") (pintype "passive"))
    )
    (net (code "152") (name "unconnected-(U1D-DDR0_ODT1-PadL5)") (class "Default")
      (node (ref "U1") (pin "L5") (pinfunction "DDR0_ODT1_L5") (pintype "passive"))
    )
    (net (code "153") (name "unconnected-(U1D-DDR0_RASN-PadF3)") (class "Default")
      (node (ref "U1") (pin "F3") (pinfunction "DDR0_RASN_F3") (pintype "passive"))
    )
    (net (code "154") (name "unconnected-(U1D-DDR0_RESETN-PadL7)") (class "Default")
      (node (ref "U1") (pin "L7") (pinfunction "DDR0_RESETN_L7") (pintype "passive"))
    )
    (net (code "155") (name "unconnected-(U1D-DDR0_WEN-PadG6)") (class "Default")
      (node (ref "U1") (pin "G6") (pinfunction "DDR0_WEN_G6") (pintype "passive"))
    )
    (net (code "156") (name "unconnected-(U1E-DDR1_A10-PadA4)") (class "Default")
      (node (ref "U1") (pin "A4") (pinfunction "DDR1_A10_A4") (pintype "passive"))
    )
    (net (code "157") (name "unconnected-(U1E-DDR1_A11-PadC5)") (class "Default")
      (node (ref "U1") (pin "C5") (pinfunction "DDR1_A11_C5") (pintype "passive"))
    )
    (net (code "158") (name "unconnected-(U1E-DDR1_A12-PadA3)") (class "Default")
      (node (ref "U1") (pin "A3") (pinfunction "DDR1_A12_A3") (pintype "passive"))
    )
    (net (code "159") (name "unconnected-(U1E-DDR1_A13-PadB4)") (class "Default")
      (node (ref "U1") (pin "B4") (pinfunction "DDR1_A13_B4") (pintype "passive"))
    )
    (net (code "160") (name "unconnected-(U1E-DDR1_A14-PadC4)") (class "Default")
      (node (ref "U1") (pin "C4") (pinfunction "DDR1_A14_C4") (pintype "passive"))
    )
    (net (code "161") (name "unconnected-(U1E-DDR1_A15-PadG8)") (class "Default")
      (node (ref "U1") (pin "G8") (pinfunction "DDR1_A15_G8") (pintype "passive"))
    )
    (net (code "162") (name "unconnected-(U1E-DDR1_BA0-PadB2)") (class "Default")
      (node (ref "U1") (pin "B2") (pinfunction "DDR1_BA0_B2") (pintype "passive"))
    )
    (net (code "163") (name "unconnected-(U1E-DDR1_BA1-PadD6)") (class "Default")
      (node (ref "U1") (pin "D6") (pinfunction "DDR1_BA1_D6") (pintype "passive"))
    )
    (net (code "164") (name "unconnected-(U1E-DDR1_BA2-PadD12)") (class "Default")
      (node (ref "U1") (pin "D12") (pinfunction "DDR1_BA2_D12") (pintype "passive"))
    )
    (net (code "165") (name "unconnected-(U1E-DDR1_CASN-PadF9)") (class "Default")
      (node (ref "U1") (pin "F9") (pinfunction "DDR1_CASN_F9") (pintype "passive"))
    )
    (net (code "166") (name "unconnected-(U1E-DDR1_CLK1N-PadE8)") (class "Default")
      (node (ref "U1") (pin "E8") (pinfunction "DDR1_CLK1N_E8") (pintype "passive"))
    )
    (net (code "167") (name "unconnected-(U1E-DDR1_CLK1P-PadE9)") (class "Default")
      (node (ref "U1") (pin "E9") (pinfunction "DDR1_CLK1P_E9") (pintype "passive"))
    )
    (net (code "168") (name "unconnected-(U1E-DDR1_CSN2-PadF11)") (class "Default")
      (node (ref "U1") (pin "F11") (pinfunction "DDR1_CSN2_F11") (pintype "passive"))
    )
    (net (code "169") (name "unconnected-(U1E-DDR1_CSN3-PadB3)") (class "Default")
      (node (ref "U1") (pin "B3") (pinfunction "DDR1_CSN3_B3") (pintype "passive"))
    )
    (net (code "170") (name "unconnected-(U1E-DDR1_ODT1-PadE11)") (class "Default")
      (node (ref "U1") (pin "E11") (pinfunction "DDR1_ODT1_E11") (pintype "passive"))
    )
    (net (code "171") (name "unconnected-(U1E-DDR1_RASN-PadC6)") (class "Default")
      (node (ref "U1") (pin "C6") (pinfunction "DDR1_RASN_C6") (pintype "passive"))
    )
    (net (code "172") (name "unconnected-(U1E-DDR1_RESETN-PadG11)") (class "Default")
      (node (ref "U1") (pin "G11") (pinfunction "DDR1_RESETN_G11") (pintype "passive"))
    )
    (net (code "173") (name "unconnected-(U1E-DDR1_WEN-PadF7)") (class "Default")
      (node (ref "U1") (pin "F7") (pinfunction "DDR1_WEN_F7") (pintype "passive"))
    )
  )
)
